# 12V-Power-Supplies.net
KiCad netlist of a schematic drawn in Altium Designer
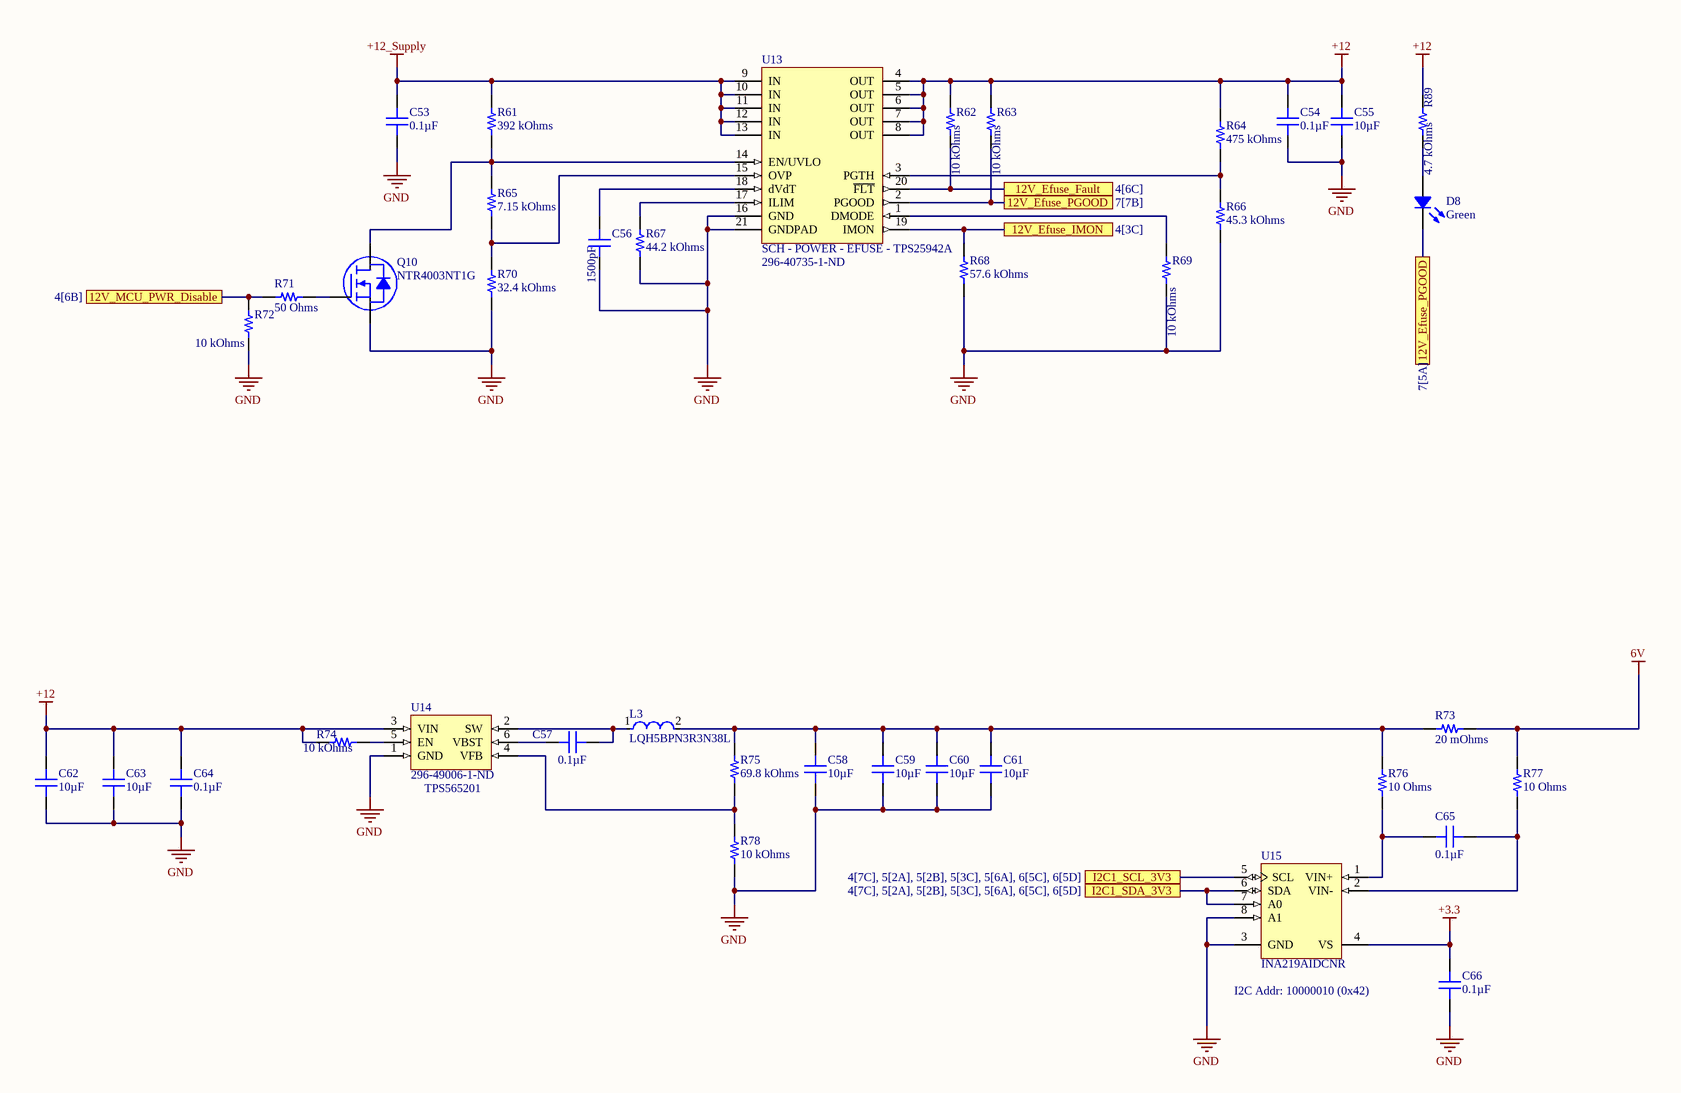
[diagram p0: 12V-Power-Supplies.SchDoc]

(export (version "E")
  (design (tool "Eeschema 10.0.6"))
  (components
    (comp (ref "C53")
      (value "0.1µF")
      (footprint "CAP 0603_1608")
      (description "CAP CER 0.1UF 25V X7R 0603")
      (fields
        (field (name "PART NUMBER") "CL10B104KA8WPNC")
        (field (name "MANUFACTURER") "Samsung Electro-Mechanics")
      )
      (libsource (lib "Celestial Altium Library - altium_library") (part "Capacitor"))
    )
    (comp (ref "C54")
      (value "0.1µF")
      (footprint "CAP 0603_1608")
      (description "CAP CER 0.1UF 25V X7R 0603")
      (fields
        (field (name "PART NUMBER") "CL10B104KA8WPNC")
        (field (name "MANUFACTURER") "Samsung Electro-Mechanics")
      )
      (libsource (lib "Celestial Altium Library - altium_library") (part "Capacitor"))
    )
    (comp (ref "C55")
      (value "10µF")
      (footprint "CAP 0805_2012")
      (description "CAP CER 10UF 16V X5R 0805")
      (fields (field (name "PART NUMBER") "CC0805KKX5R7BB106") (field (name "MANUFACTURER") "Yageo"))
      (libsource (lib "Celestial Altium Library - altium_library") (part "Capacitor"))
    )
    (comp (ref "C56")
      (value "1500pF")
      (footprint "CAP 0603_1608")
      (description "CAP CER 1500PF 25V X7R 0603")
      (fields (field (name "PART NUMBER") "CC0603JRX7R8BB152") (field (name "MANUFACTURER") "Yageo"))
      (libsource (lib "Celestial Altium Library - altium_library") (part "Capacitor"))
    )
    (comp (ref "C57")
      (value "0.1µF")
      (footprint "CAP 0603_1608")
      (description "CAP CER 0.1UF 25V X7R 0603")
      (fields
        (field (name "PART NUMBER") "CL10B104KA8WPNC")
        (field (name "MANUFACTURER") "Samsung Electro-Mechanics")
      )
      (libsource (lib "Celestial Altium Library - altium_library") (part "Capacitor"))
    )
    (comp (ref "C58")
      (value "10µF")
      (footprint "CAP 0805_2012")
      (description "CAP CER 10UF 16V X5R 0805")
      (fields (field (name "PART NUMBER") "CC0805KKX5R7BB106") (field (name "MANUFACTURER") "Yageo"))
      (libsource (lib "Celestial Altium Library - altium_library") (part "Capacitor"))
    )
    (comp (ref "C59")
      (value "10µF")
      (footprint "CAP 0805_2012")
      (description "CAP CER 10UF 16V X5R 0805")
      (fields (field (name "PART NUMBER") "CC0805KKX5R7BB106") (field (name "MANUFACTURER") "Yageo"))
      (libsource (lib "Celestial Altium Library - altium_library") (part "Capacitor"))
    )
    (comp (ref "C60")
      (value "10µF")
      (footprint "CAP 0805_2012")
      (description "CAP CER 10UF 16V X5R 0805")
      (fields (field (name "PART NUMBER") "CC0805KKX5R7BB106") (field (name "MANUFACTURER") "Yageo"))
      (libsource (lib "Celestial Altium Library - altium_library") (part "Capacitor"))
    )
    (comp (ref "C61")
      (value "10µF")
      (footprint "CAP 0805_2012")
      (description "CAP CER 10UF 16V X5R 0805")
      (fields (field (name "PART NUMBER") "CC0805KKX5R7BB106") (field (name "MANUFACTURER") "Yageo"))
      (libsource (lib "Celestial Altium Library - altium_library") (part "Capacitor"))
    )
    (comp (ref "C62")
      (value "10µF")
      (footprint "CAP 0805_2012")
      (description "CAP CER 10UF 16V X5R 0805")
      (fields (field (name "PART NUMBER") "CC0805KKX5R7BB106") (field (name "MANUFACTURER") "Yageo"))
      (libsource (lib "Celestial Altium Library - altium_library") (part "Capacitor"))
    )
    (comp (ref "C63")
      (value "10µF")
      (footprint "CAP 0805_2012")
      (description "CAP CER 10UF 16V X5R 0805")
      (fields (field (name "PART NUMBER") "CC0805KKX5R7BB106") (field (name "MANUFACTURER") "Yageo"))
      (libsource (lib "Celestial Altium Library - altium_library") (part "Capacitor"))
    )
    (comp (ref "C64")
      (value "0.1µF")
      (footprint "CAP 0603_1608")
      (description "CAP CER 0.1UF 25V X7R 0603")
      (fields
        (field (name "PART NUMBER") "CL10B104KA8WPNC")
        (field (name "MANUFACTURER") "Samsung Electro-Mechanics")
      )
      (libsource (lib "Celestial Altium Library - altium_library") (part "Capacitor"))
    )
    (comp (ref "C65")
      (value "0.1µF")
      (footprint "CAP 0603_1608")
      (description "CAP CER 0.1UF 25V X7R 0603")
      (fields
        (field (name "PART NUMBER") "CL10B104KA8WPNC")
        (field (name "MANUFACTURER") "Samsung Electro-Mechanics")
      )
      (libsource (lib "Celestial Altium Library - altium_library") (part "Capacitor"))
    )
    (comp (ref "C66")
      (value "0.1µF")
      (footprint "CAP 0603_1608")
      (description "CAP CER 0.1UF 25V X7R 0603")
      (fields
        (field (name "PART NUMBER") "CL10B104KA8WPNC")
        (field (name "MANUFACTURER") "Samsung Electro-Mechanics")
      )
      (libsource (lib "Celestial Altium Library - altium_library") (part "Capacitor"))
    )
    (comp (ref "D8")
      (value "Green")
      (footprint "LED 0603_1608 GREEN")
      (description "LED GREEN CLEAR CHIP SMD")
      (fields (field (name "PART NUMBER") "LTST-C193KGKT-5A") (field (name "MANUFACTURER") "Lite-On Inc."))
      (libsource (lib "Celestial Altium Library - altium_library") (part "LED"))
    )
    (comp (ref "L3")
      (value "LQH5BPN3R3N38L")
      (footprint "FP-LQH5BPN_38-MFG")
      (description "Wire Wound Ferrite Inductor for Power Lines 3.3μH ±30% 0.0252Ω 4000mA 2020")
      (fields (field (name "TOLERANCE") "30%"))
      (libsource (lib "Altium Content Vault") (part "725321dda6339637d4d059423bc1c3c"))
    )
    (comp (ref "Q10")
      (value "NTR4003NT1G")
      (footprint "ON SEMI SOT-23-3")
      (description "MOSFET N-CH 30V 500MA SOT-23")
      (fields (field (name "MANUFACTURER") "ON Semiconductor"))
      (libsource (lib "Celestial Altium Library - altium_library") (part "ON SEMI MOSFET N-CH SOT-23-3"))
    )
    (comp (ref "R61")
      (value "392 kOhms")
      (footprint "RES 0603_1608")
      (description "RES 392K OHM 1% 1/10W 0603")
      (fields
        (field (name "PART NUMBER") "RMCF0603FT392K")
        (field (name "MANUFACTURER") "Stackpole Electronics Inc")
      )
      (libsource (lib "Celestial Altium Library - altium_library") (part "Resistor"))
    )
    (comp (ref "R62")
      (value "10 kOhms")
      (footprint "RES 0603_1608")
      (description "RES 10K OHM 5% 1/10W 0603")
      (fields
        (field (name "PART NUMBER") "RMCF0603JT10K0")
        (field (name "MANUFACTURER") "Stackpole Electronics Inc")
      )
      (libsource (lib "Celestial Altium Library - altium_library") (part "Resistor"))
    )
    (comp (ref "R63")
      (value "10 kOhms")
      (footprint "RES 0603_1608")
      (description "RES 10K OHM 5% 1/10W 0603")
      (fields
        (field (name "PART NUMBER") "RMCF0603JT10K0")
        (field (name "MANUFACTURER") "Stackpole Electronics Inc")
      )
      (libsource (lib "Celestial Altium Library - altium_library") (part "Resistor"))
    )
    (comp (ref "R64")
      (value "475 kOhms")
      (footprint "RES 0603_1608")
      (description "RES 475K OHM 1% 1/10W 0603")
      (fields
        (field (name "PART NUMBER") "RMCF0603FT475K")
        (field (name "MANUFACTURER") "Stackpole Electronics Inc")
      )
      (libsource (lib "Celestial Altium Library - altium_library") (part "Resistor"))
    )
    (comp (ref "R65")
      (value "7.15 kOhms")
      (footprint "RES 0603_1608")
      (description "RES SMD 7.15K OHM 0.1% 1/5W 0603")
      (fields
        (field (name "PART NUMBER") "ERJ-PB3B7151V")
        (field (name "MANUFACTURER") "Panasonic Electronic Components")
      )
      (libsource (lib "Celestial Altium Library - altium_library") (part "Resistor"))
    )
    (comp (ref "R66")
      (value "45.3 kOhms")
      (footprint "RES 0603_1608")
      (description "RES 45.3K OHM 1% 1/10W 0603")
      (fields
        (field (name "PART NUMBER") "RMCF0603FT45K3")
        (field (name "MANUFACTURER") "Stackpole Electronics Inc")
      )
      (libsource (lib "Celestial Altium Library - altium_library") (part "Resistor"))
    )
    (comp (ref "R67")
      (value "44.2 kOhms")
      (footprint "RES 0603_1608")
      (description "RES 44.2K OHM 1% 1/10W 0603")
      (fields
        (field (name "PART NUMBER") "RMCF0603FT44K2")
        (field (name "MANUFACTURER") "Stackpole Electronics Inc")
      )
      (libsource (lib "Celestial Altium Library - altium_library") (part "Resistor"))
    )
    (comp (ref "R68")
      (value "57.6 kOhms")
      (footprint "RES 0603_1608")
      (description "RES 57.6K OHM 1% 1/10W 0603")
      (fields
        (field (name "PART NUMBER") "RMCF0603FT57K6")
        (field (name "MANUFACTURER") "Stackpole Electronics Inc")
      )
      (libsource (lib "Celestial Altium Library - altium_library") (part "Resistor"))
    )
    (comp (ref "R69")
      (value "10 kOhms")
      (footprint "RES 0603_1608")
      (description "RES 10K OHM 5% 1/10W 0603")
      (fields
        (field (name "PART NUMBER") "RMCF0603JT10K0")
        (field (name "MANUFACTURER") "Stackpole Electronics Inc")
      )
      (libsource (lib "Celestial Altium Library - altium_library") (part "Resistor"))
    )
    (comp (ref "R70")
      (value "32.4 kOhms")
      (footprint "RES 0603_1608")
      (description "RES SMD 32.4K OHM 0.1% 1/5W 0603")
      (fields
        (field (name "PART NUMBER") "ERJ-PB3B3242V")
        (field (name "MANUFACTURER") "Panasonic Electronic Components")
      )
      (libsource (lib "Celestial Altium Library - altium_library") (part "Resistor"))
    )
    (comp (ref "R71")
      (value "50 Ohms")
      (footprint "RES 0603_1608")
      (description "RES SMD 50 OHM 1% 1/10W 0603")
      (fields (field (name "PART NUMBER") "CRCW060350R0FKEA") (field (name "MANUFACTURER") "Vishay Dale"))
      (libsource (lib "Celestial Altium Library - altium_library") (part "Resistor"))
    )
    (comp (ref "R72")
      (value "10 kOhms")
      (footprint "RES 0603_1608")
      (description "RES 10K OHM 5% 1/10W 0603")
      (fields
        (field (name "PART NUMBER") "RMCF0603JT10K0")
        (field (name "MANUFACTURER") "Stackpole Electronics Inc")
      )
      (libsource (lib "Celestial Altium Library - altium_library") (part "Resistor"))
    )
    (comp (ref "R73")
      (value "20 mOhms")
      (footprint "RES 0805_2012")
      (description "0805 CURRENT SENSING RES. 0.5%,")
      (fields
        (field (name "PART NUMBER") "ERJ-6CWDR020V")
        (field (name "MANUFACTURER") "Panasonic Electronic Components")
      )
      (libsource (lib "Celestial Altium Library - altium_library") (part "Resistor"))
    )
    (comp (ref "R74")
      (value "10 kOhms")
      (footprint "RES 0603_1608")
      (description "RES 10K OHM 5% 1/10W 0603")
      (fields
        (field (name "PART NUMBER") "RMCF0603JT10K0")
        (field (name "MANUFACTURER") "Stackpole Electronics Inc")
      )
      (libsource (lib "Celestial Altium Library - altium_library") (part "Resistor"))
    )
    (comp (ref "R75")
      (value "69.8 kOhms")
      (footprint "RES 0603_1608")
      (description "RES 69.8K OHM 1% 1/10W 0603")
      (fields
        (field (name "PART NUMBER") "RMCF0603FT69K8")
        (field (name "MANUFACTURER") "Stackpole Electronics Inc")
      )
      (libsource (lib "Celestial Altium Library - altium_library") (part "Resistor"))
    )
    (comp (ref "R76")
      (value "10 Ohms")
      (footprint "RES 0603_1608")
      (description "CRGCQ 0603 10R 1%")
      (fields
        (field (name "PART NUMBER") "CRGCQ0603F10R")
        (field (name "MANUFACTURER") "TE Connectivity Passive Product")
      )
      (libsource (lib "Celestial Altium Library - altium_library") (part "Resistor"))
    )
    (comp (ref "R77")
      (value "10 Ohms")
      (footprint "RES 0603_1608")
      (description "CRGCQ 0603 10R 1%")
      (fields
        (field (name "PART NUMBER") "CRGCQ0603F10R")
        (field (name "MANUFACTURER") "TE Connectivity Passive Product")
      )
      (libsource (lib "Celestial Altium Library - altium_library") (part "Resistor"))
    )
    (comp (ref "R78")
      (value "10 kOhms")
      (footprint "RES 0603_1608")
      (description "RES 10K OHM 1% 1/10W 0603")
      (fields
        (field (name "PART NUMBER") "RMCF0603FT10K0")
        (field (name "MANUFACTURER") "Stackpole Electronics Inc")
      )
      (libsource (lib "Celestial Altium Library - altium_library") (part "Resistor"))
    )
    (comp (ref "R89")
      (value "4.7 kOhms")
      (footprint "RES 0603_1608")
      (description "RES 4.7K OHM 1% 1/10W 0603")
      (fields
        (field (name "PART NUMBER") "RMCF0603FT4K70")
        (field (name "MANUFACTURER") "Stackpole Electronics Inc")
      )
      (libsource (lib "Celestial Altium Library - altium_library") (part "Resistor"))
    )
    (comp (ref "U13")
      (value "SCH - POWER - EFUSE - TPS25942A")
      (footprint "PCB - LEADLESS - QFN - TI 20-WQFN")
      (fields (field (name "SUPPLIER PART NUMBER 1") "296-40735-1-ND"))
      (libsource (lib "HAB_ICs") (part "SCH - POWER - EFUSE - TPS25942A"))
    )
    (comp (ref "U14")
      (value "SCH - REGULATOR - BUCK - TI TPS565201DDCR")
      (footprint "PCB - LEADS - SOT- TI TSOT-23-6")
      (fields (field (name "SUPPLIER PART NUMBER 1") "296-49006-1-ND"))
      (libsource (lib "HAB_ICs") (part "SCH - REGULATOR - BUCK - TI TPS565201DDCR"))
    )
    (comp (ref "U15")
      (value "INA219AIDCNR")
      (footprint "DCN0008A_M")
      (fields (field (name "MANUFACTURER") "Texas Instruments"))
      (libsource (lib "Altium Content Vault") (part "TI-INA219DCN8"))
    )
  )
  (nets
    (net (code "1") (name "+3.3") (class "Default")
      (node (ref "C66") (pin "2") (pinfunction "2_2") (pintype "passive"))
      (node (ref "U15") (pin "4") (pinfunction "VS_4") (pintype "power_in"))
    )
    (net (code "2") (name "+12") (class "Default")
      (node (ref "C54") (pin "2") (pinfunction "2_2") (pintype "passive"))
      (node (ref "C55") (pin "2") (pinfunction "2_2") (pintype "passive"))
      (node (ref "C62") (pin "2") (pinfunction "2_2") (pintype "passive"))
      (node (ref "C63") (pin "2") (pinfunction "2_2") (pintype "passive"))
      (node (ref "C64") (pin "1") (pinfunction "1_1") (pintype "passive"))
      (node (ref "R62") (pin "2") (pinfunction "2_2") (pintype "passive"))
      (node (ref "R63") (pin "2") (pinfunction "2_2") (pintype "passive"))
      (node (ref "R64") (pin "2") (pinfunction "2_2") (pintype "passive"))
      (node (ref "R74") (pin "1") (pinfunction "1_1") (pintype "passive"))
      (node (ref "R89") (pin "2") (pinfunction "2_2") (pintype "passive"))
      (node (ref "U13") (pin "4") (pinfunction "OUT_4") (pintype "power_in"))
      (node (ref "U13") (pin "5") (pinfunction "OUT_5") (pintype "power_in"))
      (node (ref "U13") (pin "6") (pinfunction "OUT_6") (pintype "power_in"))
      (node (ref "U13") (pin "7") (pinfunction "OUT_7") (pintype "power_in"))
      (node (ref "U13") (pin "8") (pinfunction "OUT_8") (pintype "power_in"))
      (node (ref "U14") (pin "3") (pinfunction "VIN_3") (pintype "input"))
    )
    (net (code "3") (name "+12_Supply") (class "Default")
      (node (ref "C53") (pin "2") (pinfunction "2_2") (pintype "passive"))
      (node (ref "R61") (pin "2") (pinfunction "2_2") (pintype "passive"))
      (node (ref "U13") (pin "10") (pinfunction "IN_10") (pintype "power_in"))
      (node (ref "U13") (pin "11") (pinfunction "IN_11") (pintype "power_in"))
      (node (ref "U13") (pin "12") (pinfunction "IN_12") (pintype "power_in"))
      (node (ref "U13") (pin "13") (pinfunction "IN_13") (pintype "power_in"))
      (node (ref "U13") (pin "9") (pinfunction "IN_9") (pintype "power_in"))
    )
    (net (code "4") (name "/12V_Efuse_Fault") (class "Default")
      (node (ref "R62") (pin "1") (pinfunction "1_1") (pintype "passive"))
      (node (ref "U13") (pin "20") (pinfunction "~{FLT}_20") (pintype "output"))
    )
    (net (code "5") (name "/12V_Efuse_IMON") (class "Default")
      (node (ref "R68") (pin "2") (pinfunction "2_2") (pintype "passive"))
      (node (ref "U13") (pin "19") (pinfunction "IMON_19") (pintype "output"))
    )
    (net (code "6") (name "/12V_Efuse_PGOOD") (class "Default")
      (node (ref "D8") (pin "2") (pinfunction "2_2") (pintype "passive"))
      (node (ref "R63") (pin "1") (pinfunction "1_1") (pintype "passive"))
      (node (ref "U13") (pin "2") (pinfunction "PGOOD_2") (pintype "output"))
    )
    (net (code "7") (name "/12V_MCU_PWR_Disable") (class "Default")
      (node (ref "R71") (pin "2") (pinfunction "2_2") (pintype "passive"))
      (node (ref "R72") (pin "2") (pinfunction "2_2") (pintype "passive"))
    )
    (net (code "8") (name "/I2C1_SCL_3V3") (class "Default")
      (node (ref "U15") (pin "5") (pinfunction "SCL_5") (pintype "bidirectional"))
    )
    (net (code "9") (name "/I2C1_SDA_3V3") (class "Default")
      (node (ref "U15") (pin "6") (pinfunction "SDA_6") (pintype "bidirectional"))
      (node (ref "U15") (pin "7") (pinfunction "A0_7") (pintype "input"))
    )
    (net (code "10") (name "6V") (class "Default")
      (node (ref "R73") (pin "2") (pinfunction "2_2") (pintype "passive"))
      (node (ref "R77") (pin "2") (pinfunction "2_2") (pintype "passive"))
    )
    (net (code "11") (name "GND") (class "Default")
      (node (ref "C53") (pin "1") (pinfunction "1_1") (pintype "passive"))
      (node (ref "C54") (pin "1") (pinfunction "1_1") (pintype "passive"))
      (node (ref "C55") (pin "1") (pinfunction "1_1") (pintype "passive"))
      (node (ref "C56") (pin "1") (pinfunction "1_1") (pintype "passive"))
      (node (ref "C58") (pin "1") (pinfunction "1_1") (pintype "passive"))
      (node (ref "C59") (pin "1") (pinfunction "1_1") (pintype "passive"))
      (node (ref "C60") (pin "1") (pinfunction "1_1") (pintype "passive"))
      (node (ref "C61") (pin "1") (pinfunction "1_1") (pintype "passive"))
      (node (ref "C62") (pin "1") (pinfunction "1_1") (pintype "passive"))
      (node (ref "C63") (pin "1") (pinfunction "1_1") (pintype "passive"))
      (node (ref "C64") (pin "2") (pinfunction "2_2") (pintype "passive"))
      (node (ref "C66") (pin "1") (pinfunction "1_1") (pintype "passive"))
      (node (ref "Q10") (pin "2") (pinfunction "S_2") (pintype "passive"))
      (node (ref "R66") (pin "1") (pinfunction "1_1") (pintype "passive"))
      (node (ref "R67") (pin "1") (pinfunction "1_1") (pintype "passive"))
      (node (ref "R68") (pin "1") (pinfunction "1_1") (pintype "passive"))
      (node (ref "R69") (pin "1") (pinfunction "1_1") (pintype "passive"))
      (node (ref "R70") (pin "1") (pinfunction "1_1") (pintype "passive"))
      (node (ref "R72") (pin "1") (pinfunction "1_1") (pintype "passive"))
      (node (ref "R78") (pin "1") (pinfunction "1_1") (pintype "passive"))
      (node (ref "U13") (pin "16") (pinfunction "GND_16") (pintype "power_in"))
      (node (ref "U13") (pin "21") (pinfunction "GNDPAD_21") (pintype "power_in"))
      (node (ref "U14") (pin "1") (pinfunction "GND_1") (pintype "input"))
      (node (ref "U15") (pin "3") (pinfunction "GND_3") (pintype "power_in"))
      (node (ref "U15") (pin "8") (pinfunction "A1_8") (pintype "input"))
    )
    (net (code "12") (name "Net-(C58-Pad2)") (class "Default")
      (node (ref "C58") (pin "2") (pinfunction "2_2") (pintype "passive"))
      (node (ref "C59") (pin "2") (pinfunction "2_2") (pintype "passive"))
      (node (ref "C60") (pin "2") (pinfunction "2_2") (pintype "passive"))
      (node (ref "C61") (pin "2") (pinfunction "2_2") (pintype "passive"))
      (node (ref "L3") (pin "2") (pinfunction "2_2") (pintype "passive"))
      (node (ref "R73") (pin "1") (pinfunction "1_1") (pintype "passive"))
      (node (ref "R75") (pin "2") (pinfunction "2_2") (pintype "passive"))
      (node (ref "R76") (pin "2") (pinfunction "2_2") (pintype "passive"))
    )
    (net (code "13") (name "Net-(D8-Pad1)") (class "Default")
      (node (ref "D8") (pin "1") (pinfunction "1_1") (pintype "passive"))
      (node (ref "R89") (pin "1") (pinfunction "1_1") (pintype "passive"))
    )
    (net (code "14") (name "Net-(Q10-D)") (class "Default")
      (node (ref "Q10") (pin "3") (pinfunction "D_3") (pintype "passive"))
      (node (ref "R61") (pin "1") (pinfunction "1_1") (pintype "passive"))
      (node (ref "R65") (pin "2") (pinfunction "2_2") (pintype "passive"))
      (node (ref "U13") (pin "14") (pinfunction "EN/UVLO_14") (pintype "input"))
    )
    (net (code "15") (name "Net-(Q10-G)") (class "Default")
      (node (ref "Q10") (pin "1") (pinfunction "G_1") (pintype "passive"))
      (node (ref "R71") (pin "1") (pinfunction "1_1") (pintype "passive"))
    )
    (net (code "16") (name "Net-(U13-DMODE)") (class "Default")
      (node (ref "R69") (pin "2") (pinfunction "2_2") (pintype "passive"))
      (node (ref "U13") (pin "1") (pinfunction "DMODE_1") (pintype "input"))
    )
    (net (code "17") (name "Net-(U13-ILIM)") (class "Default")
      (node (ref "R67") (pin "2") (pinfunction "2_2") (pintype "passive"))
      (node (ref "U13") (pin "17") (pinfunction "ILIM_17") (pintype "input"))
    )
    (net (code "18") (name "Net-(U13-OVP)") (class "Default")
      (node (ref "R65") (pin "1") (pinfunction "1_1") (pintype "passive"))
      (node (ref "R70") (pin "2") (pinfunction "2_2") (pintype "passive"))
      (node (ref "U13") (pin "15") (pinfunction "OVP_15") (pintype "input"))
    )
    (net (code "19") (name "Net-(U13-PGTH)") (class "Default")
      (node (ref "R64") (pin "1") (pinfunction "1_1") (pintype "passive"))
      (node (ref "R66") (pin "2") (pinfunction "2_2") (pintype "passive"))
      (node (ref "U13") (pin "3") (pinfunction "PGTH_3") (pintype "input"))
    )
    (net (code "20") (name "Net-(U13-dVdT)") (class "Default")
      (node (ref "C56") (pin "2") (pinfunction "2_2") (pintype "passive"))
      (node (ref "U13") (pin "18") (pinfunction "dVdT_18") (pintype "input"))
    )
    (net (code "21") (name "Net-(U14-EN)") (class "Default")
      (node (ref "R74") (pin "2") (pinfunction "2_2") (pintype "passive"))
      (node (ref "U14") (pin "5") (pinfunction "EN_5") (pintype "input"))
    )
    (net (code "22") (name "Net-(U14-SW)") (class "Default")
      (node (ref "C57") (pin "1") (pinfunction "1_1") (pintype "passive"))
      (node (ref "L3") (pin "1") (pinfunction "1_1") (pintype "passive"))
      (node (ref "U14") (pin "2") (pinfunction "SW_2") (pintype "input"))
    )
    (net (code "23") (name "Net-(U14-VBST)") (class "Default")
      (node (ref "C57") (pin "2") (pinfunction "2_2") (pintype "passive"))
      (node (ref "U14") (pin "6") (pinfunction "VBST_6") (pintype "input"))
    )
    (net (code "24") (name "Net-(U14-VFB)") (class "Default")
      (node (ref "R75") (pin "1") (pinfunction "1_1") (pintype "passive"))
      (node (ref "R78") (pin "2") (pinfunction "2_2") (pintype "passive"))
      (node (ref "U14") (pin "4") (pinfunction "VFB_4") (pintype "input"))
    )
    (net (code "25") (name "Net-(U15-VIN+)") (class "Default")
      (node (ref "C65") (pin "2") (pinfunction "2_2") (pintype "passive"))
      (node (ref "R76") (pin "1") (pinfunction "1_1") (pintype "passive"))
      (node (ref "U15") (pin "1") (pinfunction "VIN+_1") (pintype "input"))
    )
    (net (code "26") (name "Net-(U15-VIN-)") (class "Default")
      (node (ref "C65") (pin "1") (pinfunction "1_1") (pintype "passive"))
      (node (ref "R77") (pin "1") (pinfunction "1_1") (pintype "passive"))
      (node (ref "U15") (pin "2") (pinfunction "VIN-_2") (pintype "input"))
    )
  )
)
